# High_Current_LEDs.net
KiCad netlist of a schematic drawn in Altium Designer
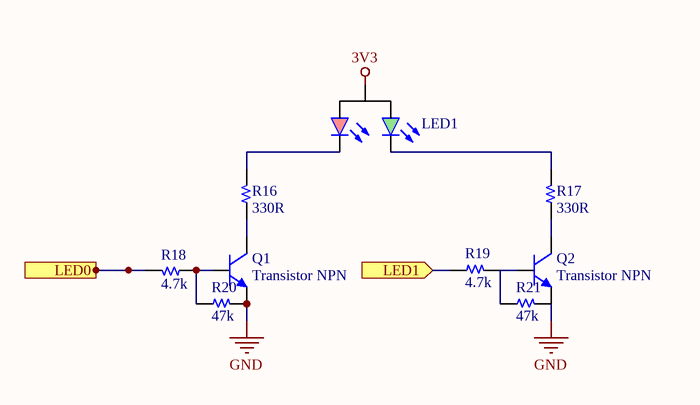
[diagram p0: High_Current_LEDs.SchDoc]

(export (version "E")
  (design (tool "Eeschema 10.0.6"))
  (components
    (comp (ref "LED1")
      (value "Led 3pin 2color")
      (footprint "LED 3PIN 2COLOR 5MM")
      (description "Typical LED 3-pin 2-color")
      (libsource (lib "chipfc_altium_libs") (part "Led 3pin 2color"))
    )
    (comp (ref "Q1")
      (value "Transistor NPN")
      (footprint "SOT-23")
      (description "NPN Bipolar Transistor")
      (libsource (lib "chipfc_altium_libs") (part "Transistor NPN"))
    )
    (comp (ref "Q2")
      (value "Transistor NPN")
      (footprint "SOT-23")
      (description "NPN Bipolar Transistor")
      (libsource (lib "chipfc_altium_libs") (part "Transistor NPN"))
    )
    (comp (ref "R16")
      (value "330R")
      (footprint "R 0805")
      (description "Resistor")
      (libsource (lib "chipfc_altium_libs") (part "Resistor"))
    )
    (comp (ref "R17")
      (value "330R")
      (footprint "R 0805")
      (description "Resistor")
      (libsource (lib "chipfc_altium_libs") (part "Resistor"))
    )
    (comp (ref "R18")
      (value "4.7k")
      (footprint "R 0805")
      (description "Resistor")
      (libsource (lib "chipfc_altium_libs") (part "Resistor"))
    )
    (comp (ref "R19")
      (value "4.7k")
      (footprint "R 0805")
      (description "Resistor")
      (libsource (lib "chipfc_altium_libs") (part "Resistor"))
    )
    (comp (ref "R20")
      (value "47k")
      (footprint "R 0805")
      (description "Resistor")
      (libsource (lib "chipfc_altium_libs") (part "Resistor"))
    )
    (comp (ref "R21")
      (value "47k")
      (footprint "R 0805")
      (description "Resistor")
      (libsource (lib "chipfc_altium_libs") (part "Resistor"))
    )
  )
  (nets
    (net (code "1") (name "/LED0") (class "Default")
      (node (ref "R18") (pin "2") (pinfunction "2_2") (pintype "passive"))
    )
    (net (code "2") (name "/LED1") (class "Default")
      (node (ref "R19") (pin "1") (pinfunction "1_1") (pintype "passive"))
    )
    (net (code "3") (name "3V3") (class "Default")
      (node (ref "LED1") (pin "2") (pinfunction "A_2") (pintype "passive"))
    )
    (net (code "4") (name "GND") (class "Default")
      (node (ref "Q1") (pin "2") (pinfunction "E_2") (pintype "passive"))
      (node (ref "Q2") (pin "2") (pinfunction "E_2") (pintype "passive"))
      (node (ref "R20") (pin "2") (pinfunction "2_2") (pintype "passive"))
      (node (ref "R21") (pin "2") (pinfunction "2_2") (pintype "passive"))
    )
    (net (code "5") (name "Net-(LED1-RK)") (class "Default")
      (node (ref "LED1") (pin "1") (pinfunction "RK_1") (pintype "passive"))
      (node (ref "R16") (pin "2") (pinfunction "2_2") (pintype "passive"))
    )
    (net (code "6") (name "Net-(LED1-YK)") (class "Default")
      (node (ref "LED1") (pin "3") (pinfunction "YK_3") (pintype "passive"))
      (node (ref "R17") (pin "2") (pinfunction "2_2") (pintype "passive"))
    )
    (net (code "7") (name "Net-(Q1-B)") (class "Default")
      (node (ref "Q1") (pin "1") (pinfunction "B_1") (pintype "passive"))
      (node (ref "R18") (pin "1") (pinfunction "1_1") (pintype "passive"))
      (node (ref "R20") (pin "1") (pinfunction "1_1") (pintype "passive"))
    )
    (net (code "8") (name "Net-(Q1-C)") (class "Default")
      (node (ref "Q1") (pin "3") (pinfunction "C_3") (pintype "passive"))
      (node (ref "R16") (pin "1") (pinfunction "1_1") (pintype "passive"))
    )
    (net (code "9") (name "Net-(Q2-B)") (class "Default")
      (node (ref "Q2") (pin "1") (pinfunction "B_1") (pintype "passive"))
      (node (ref "R19") (pin "2") (pinfunction "2_2") (pintype "passive"))
      (node (ref "R21") (pin "1") (pinfunction "1_1") (pintype "passive"))
    )
    (net (code "10") (name "Net-(Q2-C)") (class "Default")
      (node (ref "Q2") (pin "3") (pinfunction "C_3") (pintype "passive"))
      (node (ref "R17") (pin "1") (pinfunction "1_1") (pintype "passive"))
    )
  )
)
